# SCH_usb-hub_2024-08-02.net
KiCad netlist of a schematic drawn in EasyEDA
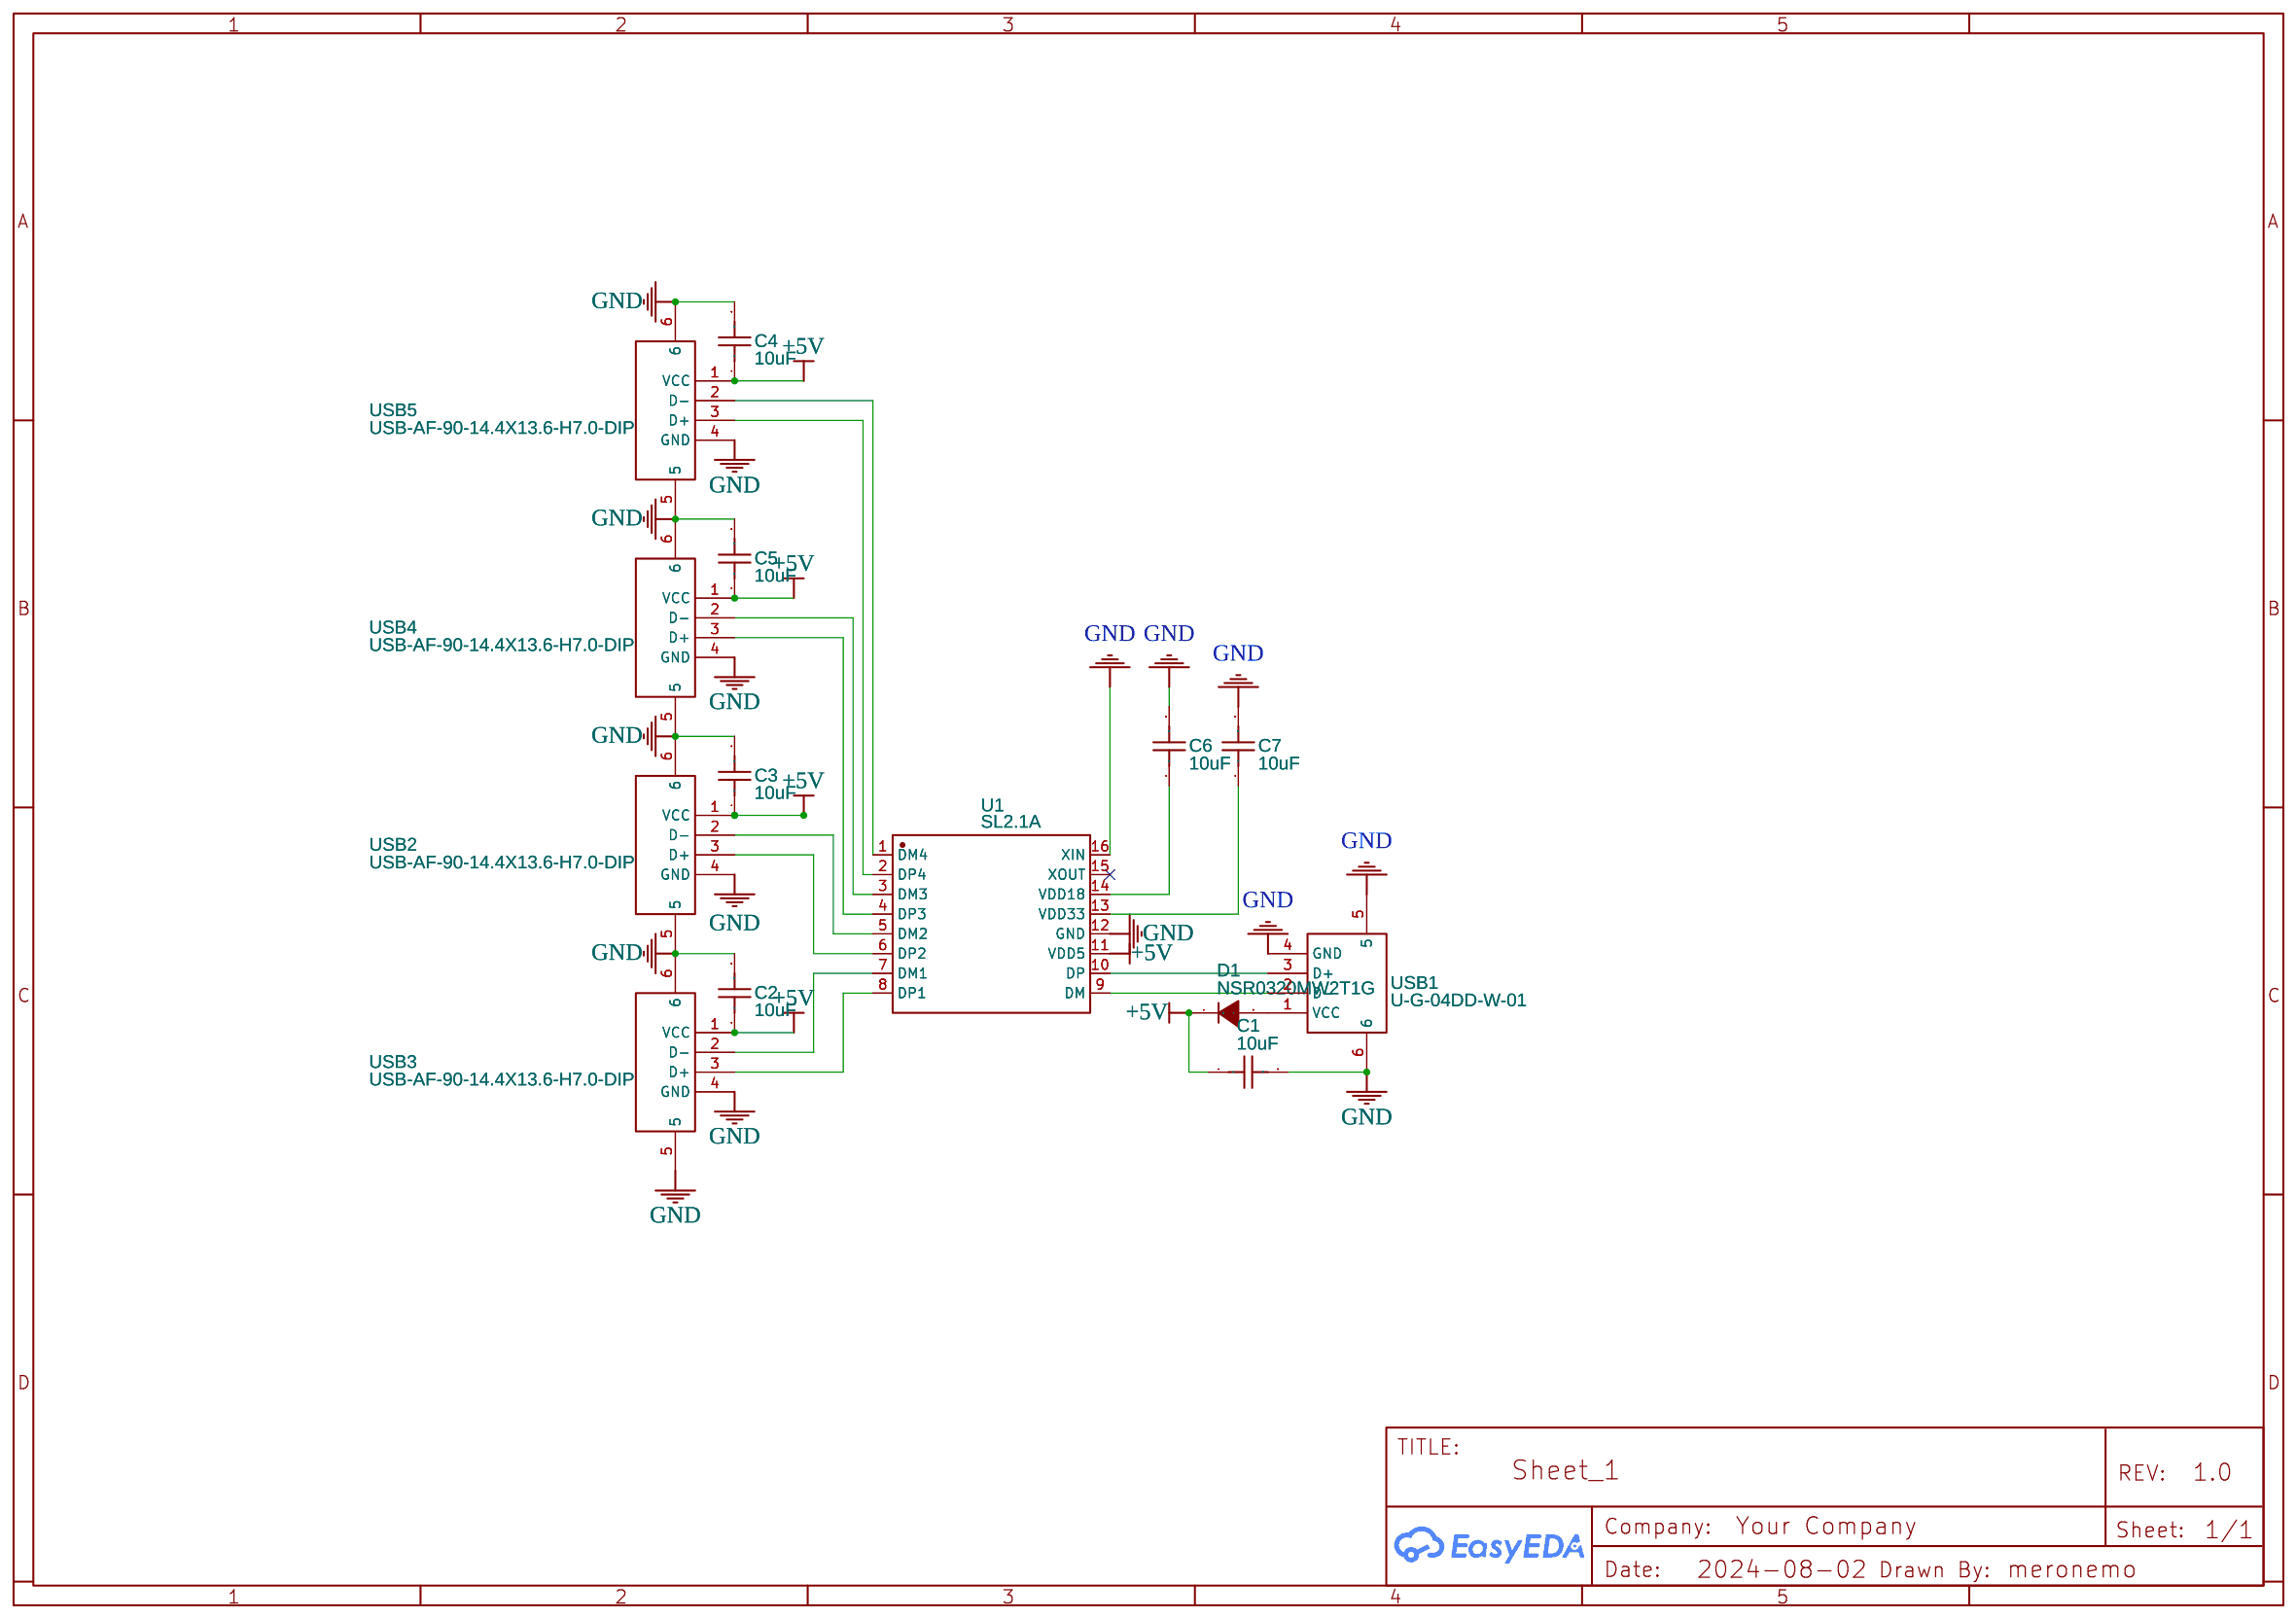
[diagram p0: schematic sheet]

(export (version "E")
  (design (tool "Eeschema 10.0.6"))
  (components
    (comp (ref "C1")
      (value "10uF")
      (fields
        (field (name "Manufacturer Part") "CL10A106KP8NNNC")
        (field (name "Manufacturer") "SAMSUNG(三星)")
      )
      (libsource (lib "") (part "CL10A106KP8NNNC_1"))
    )
    (comp (ref "C2")
      (value "10uF")
      (fields
        (field (name "Manufacturer Part") "CL10A106KP8NNNC")
        (field (name "Manufacturer") "SAMSUNG(三星)")
      )
      (libsource (lib "") (part "CL10A106KP8NNNC"))
    )
    (comp (ref "C3")
      (value "10uF")
      (fields
        (field (name "Manufacturer Part") "CL10A106KP8NNNC")
        (field (name "Manufacturer") "SAMSUNG(三星)")
      )
      (libsource (lib "") (part "CL10A106KP8NNNC"))
    )
    (comp (ref "C4")
      (value "10uF")
      (fields
        (field (name "Manufacturer Part") "CL10A106KP8NNNC")
        (field (name "Manufacturer") "SAMSUNG(三星)")
      )
      (libsource (lib "") (part "CL10A106KP8NNNC"))
    )
    (comp (ref "C5")
      (value "10uF")
      (fields
        (field (name "Manufacturer Part") "CL10A106KP8NNNC")
        (field (name "Manufacturer") "SAMSUNG(三星)")
      )
      (libsource (lib "") (part "CL10A106KP8NNNC"))
    )
    (comp (ref "C6")
      (value "10uF")
      (fields
        (field (name "Manufacturer Part") "CL10A106KP8NNNC")
        (field (name "Manufacturer") "SAMSUNG(三星)")
      )
      (libsource (lib "") (part "CL10A106KP8NNNC"))
    )
    (comp (ref "C7")
      (value "10uF")
      (fields
        (field (name "Manufacturer Part") "CL10A106KP8NNNC")
        (field (name "Manufacturer") "SAMSUNG(三星)")
      )
      (libsource (lib "") (part "CL10A106KP8NNNC"))
    )
    (comp (ref "D1")
      (value "NSR0320MW2T1G")
      (fields (field (name "Manufacturer") "onsemi(安森美)"))
      (libsource (lib "") (part "NSR0320MW2T1G"))
    )
    (comp (ref "U1")
      (value "SL2.1A")
      (fields (field (name "Manufacturer") "CoreChips(和芯润德)"))
      (libsource (lib "") (part "SL2.1A"))
    )
    (comp (ref "USB1")
      (value "U-G-04DD-W-01")
      (fields (field (name "Manufacturer Part") "U-G-O4DD-W-1") (field (name "Manufacturer") "韩国韩荣"))
      (libsource (lib "") (part "U-G-04DD-W-01"))
    )
    (comp (ref "USB2")
      (value "USB-AF-90-14.4X13.6-H7.0-DIP")
      (fields (field (name "Manufacturer Part") "903-131A1011D10100") (field (name "Manufacturer") "精拓金"))
      (libsource (lib "") (part "USB-AF-90-14.4X13.6-H7.0-DIP"))
    )
    (comp (ref "USB3")
      (value "USB-AF-90-14.4X13.6-H7.0-DIP")
      (fields (field (name "Manufacturer Part") "903-131A1011D10100") (field (name "Manufacturer") "精拓金"))
      (libsource (lib "") (part "USB-AF-90-14.4X13.6-H7.0-DIP"))
    )
    (comp (ref "USB4")
      (value "USB-AF-90-14.4X13.6-H7.0-DIP")
      (fields (field (name "Manufacturer Part") "903-131A1011D10100") (field (name "Manufacturer") "精拓金"))
      (libsource (lib "") (part "USB-AF-90-14.4X13.6-H7.0-DIP"))
    )
    (comp (ref "USB5")
      (value "USB-AF-90-14.4X13.6-H7.0-DIP")
      (fields (field (name "Manufacturer Part") "903-131A1011D10100") (field (name "Manufacturer") "精拓金"))
      (libsource (lib "") (part "USB-AF-90-14.4X13.6-H7.0-DIP"))
    )
  )
  (nets
    (net (code "1") (name "+5V") (class "Default")
      (node (ref "C1") (pin "1") (pinfunction "1_1") (pintype "unspecified"))
      (node (ref "C2") (pin "1") (pinfunction "1_1") (pintype "unspecified"))
      (node (ref "C3") (pin "1") (pinfunction "1_1") (pintype "unspecified"))
      (node (ref "C4") (pin "1") (pinfunction "1_1") (pintype "unspecified"))
      (node (ref "C5") (pin "1") (pinfunction "1_1") (pintype "unspecified"))
      (node (ref "D1") (pin "1") (pinfunction "C_1") (pintype "unspecified"))
      (node (ref "U1") (pin "11") (pinfunction "VDD5_11") (pintype "unspecified"))
      (node (ref "USB2") (pin "1") (pinfunction "VCC_1") (pintype "unspecified"))
      (node (ref "USB3") (pin "1") (pinfunction "VCC_1") (pintype "unspecified"))
      (node (ref "USB4") (pin "1") (pinfunction "VCC_1") (pintype "unspecified"))
      (node (ref "USB5") (pin "1") (pinfunction "VCC_1") (pintype "unspecified"))
    )
    (net (code "2") (name "GND") (class "Default")
      (node (ref "C1") (pin "2") (pinfunction "2_2") (pintype "unspecified"))
      (node (ref "C2") (pin "2") (pinfunction "2_2") (pintype "unspecified"))
      (node (ref "C3") (pin "2") (pinfunction "2_2") (pintype "unspecified"))
      (node (ref "C4") (pin "2") (pinfunction "2_2") (pintype "unspecified"))
      (node (ref "C5") (pin "2") (pinfunction "2_2") (pintype "unspecified"))
      (node (ref "C6") (pin "2") (pinfunction "2_2") (pintype "unspecified"))
      (node (ref "C7") (pin "2") (pinfunction "2_2") (pintype "unspecified"))
      (node (ref "U1") (pin "12") (pinfunction "GND_12") (pintype "unspecified"))
      (node (ref "U1") (pin "16") (pinfunction "XIN_16") (pintype "unspecified"))
      (node (ref "USB1") (pin "4") (pinfunction "GND_4") (pintype "unspecified"))
      (node (ref "USB1") (pin "5") (pinfunction "5_5") (pintype "unspecified"))
      (node (ref "USB1") (pin "6") (pinfunction "6_6") (pintype "unspecified"))
      (node (ref "USB2") (pin "4") (pinfunction "GND_4") (pintype "unspecified"))
      (node (ref "USB2") (pin "5") (pinfunction "5_5") (pintype "unspecified"))
      (node (ref "USB2") (pin "6") (pinfunction "6_6") (pintype "unspecified"))
      (node (ref "USB3") (pin "4") (pinfunction "GND_4") (pintype "unspecified"))
      (node (ref "USB3") (pin "5") (pinfunction "5_5") (pintype "unspecified"))
      (node (ref "USB3") (pin "6") (pinfunction "6_6") (pintype "unspecified"))
      (node (ref "USB4") (pin "4") (pinfunction "GND_4") (pintype "unspecified"))
      (node (ref "USB4") (pin "5") (pinfunction "5_5") (pintype "unspecified"))
      (node (ref "USB4") (pin "6") (pinfunction "6_6") (pintype "unspecified"))
      (node (ref "USB5") (pin "4") (pinfunction "GND_4") (pintype "unspecified"))
      (node (ref "USB5") (pin "5") (pinfunction "5_5") (pintype "unspecified"))
      (node (ref "USB5") (pin "6") (pinfunction "6_6") (pintype "unspecified"))
    )
    (net (code "3") (name "Net-(D1-A)") (class "Default")
      (node (ref "D1") (pin "2") (pinfunction "A_2") (pintype "unspecified"))
      (node (ref "USB1") (pin "1") (pinfunction "VCC_1") (pintype "unspecified"))
    )
    (net (code "4") (name "Net-(U1-DM)") (class "Default")
      (node (ref "U1") (pin "9") (pinfunction "DM_9") (pintype "unspecified"))
      (node (ref "USB1") (pin "2") (pinfunction "D-_2") (pintype "unspecified"))
    )
    (net (code "5") (name "Net-(U1-DM1)") (class "Default")
      (node (ref "U1") (pin "7") (pinfunction "DM1_7") (pintype "unspecified"))
      (node (ref "USB3") (pin "2") (pinfunction "D-_2") (pintype "unspecified"))
    )
    (net (code "6") (name "Net-(U1-DM2)") (class "Default")
      (node (ref "U1") (pin "5") (pinfunction "DM2_5") (pintype "unspecified"))
      (node (ref "USB2") (pin "2") (pinfunction "D-_2") (pintype "unspecified"))
    )
    (net (code "7") (name "Net-(U1-DM3)") (class "Default")
      (node (ref "U1") (pin "3") (pinfunction "DM3_3") (pintype "unspecified"))
      (node (ref "USB4") (pin "2") (pinfunction "D-_2") (pintype "unspecified"))
    )
    (net (code "8") (name "Net-(U1-DM4)") (class "Default")
      (node (ref "U1") (pin "1") (pinfunction "DM4_1") (pintype "unspecified"))
      (node (ref "USB5") (pin "2") (pinfunction "D-_2") (pintype "unspecified"))
    )
    (net (code "9") (name "Net-(U1-DP)") (class "Default")
      (node (ref "U1") (pin "10") (pinfunction "DP_10") (pintype "unspecified"))
      (node (ref "USB1") (pin "3") (pinfunction "D+_3") (pintype "unspecified"))
    )
    (net (code "10") (name "Net-(U1-DP1)") (class "Default")
      (node (ref "U1") (pin "8") (pinfunction "DP1_8") (pintype "unspecified"))
      (node (ref "USB3") (pin "3") (pinfunction "D+_3") (pintype "unspecified"))
    )
    (net (code "11") (name "Net-(U1-DP2)") (class "Default")
      (node (ref "U1") (pin "6") (pinfunction "DP2_6") (pintype "unspecified"))
      (node (ref "USB2") (pin "3") (pinfunction "D+_3") (pintype "unspecified"))
    )
    (net (code "12") (name "Net-(U1-DP3)") (class "Default")
      (node (ref "U1") (pin "4") (pinfunction "DP3_4") (pintype "unspecified"))
      (node (ref "USB4") (pin "3") (pinfunction "D+_3") (pintype "unspecified"))
    )
    (net (code "13") (name "Net-(U1-DP4)") (class "Default")
      (node (ref "U1") (pin "2") (pinfunction "DP4_2") (pintype "unspecified"))
      (node (ref "USB5") (pin "3") (pinfunction "D+_3") (pintype "unspecified"))
    )
    (net (code "14") (name "Net-(U1-VDD18)") (class "Default")
      (node (ref "C6") (pin "1") (pinfunction "1_1") (pintype "unspecified"))
      (node (ref "U1") (pin "14") (pinfunction "VDD18_14") (pintype "unspecified"))
    )
    (net (code "15") (name "Net-(U1-VDD33)") (class "Default")
      (node (ref "C7") (pin "1") (pinfunction "1_1") (pintype "unspecified"))
      (node (ref "U1") (pin "13") (pinfunction "VDD33_13") (pintype "unspecified"))
    )
    (net (code "16") (name "unconnected-(U1-XOUT-Pad15)") (class "Default")
      (node (ref "U1") (pin "15") (pinfunction "XOUT_15") (pintype "unspecified+no_connect"))
    )
  )
)
